# 03_BOOT.net
KiCad netlist of a schematic drawn in Altium Designer
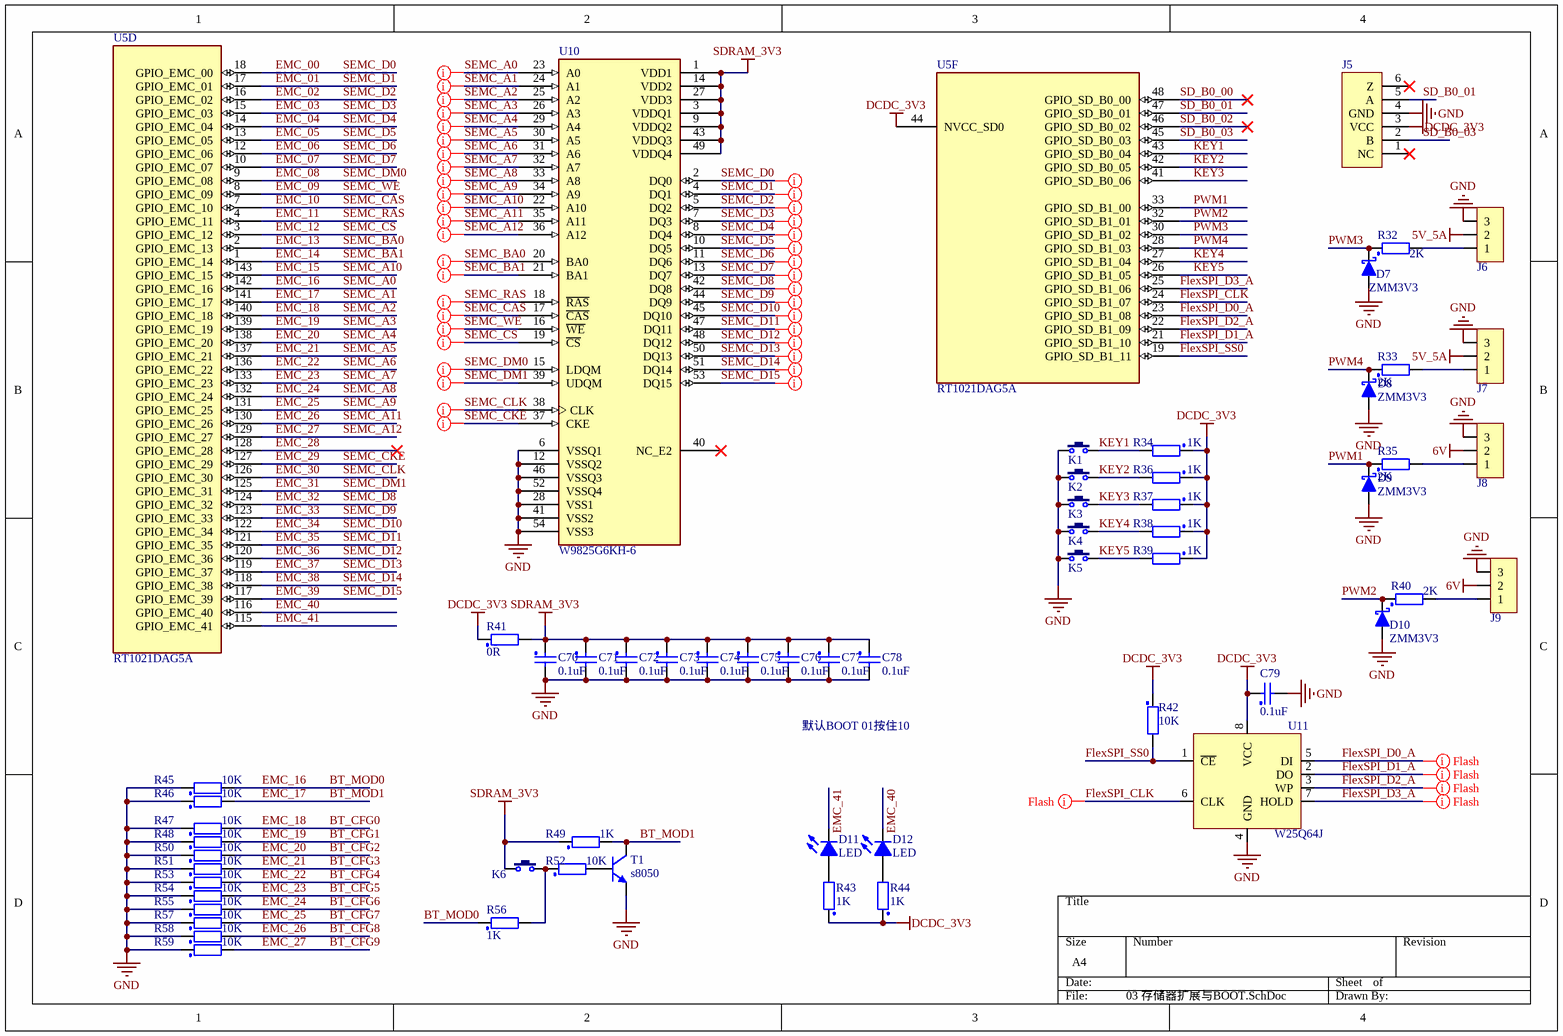
[diagram p0: 03 存储器扩展与BOOT.SchDoc]

(export (version "E")
  (design (tool "Eeschema 10.0.6"))
  (components
    (comp (ref "C70")
      (value "0.1uF")
      (footprint "cap0603")
      (description "贴片电容")
      (fields (field (name "PUBLISHER") "Altium Limited"))
      (libsource (lib "元件库") (part "Cap"))
    )
    (comp (ref "C71")
      (value "0.1uF")
      (footprint "cap0603")
      (description "贴片电容")
      (fields (field (name "PUBLISHER") "Altium Limited"))
      (libsource (lib "元件库") (part "Cap"))
    )
    (comp (ref "C72")
      (value "0.1uF")
      (footprint "cap0603")
      (description "贴片电容")
      (fields (field (name "PUBLISHER") "Altium Limited"))
      (libsource (lib "元件库") (part "Cap"))
    )
    (comp (ref "C73")
      (value "0.1uF")
      (footprint "cap0603")
      (description "贴片电容")
      (fields (field (name "PUBLISHER") "Altium Limited"))
      (libsource (lib "元件库") (part "Cap"))
    )
    (comp (ref "C74")
      (value "0.1uF")
      (footprint "cap0603")
      (description "贴片电容")
      (fields (field (name "PUBLISHER") "Altium Limited"))
      (libsource (lib "元件库") (part "Cap"))
    )
    (comp (ref "C75")
      (value "0.1uF")
      (footprint "cap0603")
      (description "贴片电容")
      (fields (field (name "PUBLISHER") "Altium Limited"))
      (libsource (lib "元件库") (part "Cap"))
    )
    (comp (ref "C76")
      (value "0.1uF")
      (footprint "cap0603")
      (description "贴片电容")
      (fields (field (name "PUBLISHER") "Altium Limited"))
      (libsource (lib "元件库") (part "Cap"))
    )
    (comp (ref "C77")
      (value "0.1uF")
      (footprint "cap0603")
      (description "贴片电容")
      (fields (field (name "PUBLISHER") "Altium Limited"))
      (libsource (lib "元件库") (part "Cap"))
    )
    (comp (ref "C78")
      (value "0.1uF")
      (footprint "cap0603")
      (description "贴片电容")
      (fields (field (name "PUBLISHER") "Altium Limited"))
      (libsource (lib "元件库") (part "Cap"))
    )
    (comp (ref "C79")
      (value "0.1uF")
      (footprint "cap0603")
      (description "贴片电容")
      (fields (field (name "PUBLISHER") "Altium Limited"))
      (libsource (lib "元件库") (part "Cap"))
    )
    (comp (ref "D7")
      (value "ZMM3V3")
      (footprint "LL34")
      (description "稳压二极管")
      (fields (field (name "PUBLISHER") "Altium Limited"))
      (libsource (lib "元件库") (part "D Schottky"))
    )
    (comp (ref "D8")
      (value "ZMM3V3")
      (footprint "LL34")
      (description "稳压二极管")
      (fields (field (name "PUBLISHER") "Altium Limited"))
      (libsource (lib "元件库") (part "D Schottky"))
    )
    (comp (ref "D9")
      (value "ZMM3V3")
      (footprint "LL34")
      (description "稳压二极管")
      (fields (field (name "PUBLISHER") "Altium Limited"))
      (libsource (lib "元件库") (part "D Schottky"))
    )
    (comp (ref "D10")
      (value "ZMM3V3")
      (footprint "LL34")
      (description "稳压二极管")
      (fields (field (name "PUBLISHER") "Altium Limited"))
      (libsource (lib "元件库") (part "D Schottky"))
    )
    (comp (ref "D11")
      (value "LED")
      (footprint "LED")
      (description "贴片LED")
      (fields (field (name "PUBLISHER") "Altium Limited"))
      (libsource (lib "元件库") (part "LED"))
    )
    (comp (ref "D12")
      (value "LED")
      (footprint "LED")
      (description "贴片LED")
      (fields (field (name "PUBLISHER") "Altium Limited"))
      (libsource (lib "元件库") (part "LED"))
    )
    (comp (ref "J5")
      (value "2x6")
      (footprint "LQ256Encoder")
      (description "2.54mm公排针")
      (libsource (lib "元件库") (part "LQ_AB256"))
    )
    (comp (ref "J6")
      (value "1X3")
      (footprint "HDR-1X3")
      (description "2.54mm公排针")
      (fields (field (name "版权归属") "源创客"))
      (libsource (lib "元件库") (part "Header 3"))
    )
    (comp (ref "J7")
      (value "1X3")
      (footprint "HDR-1X3")
      (description "2.54mm公排针")
      (fields (field (name "版权归属") "源创客"))
      (libsource (lib "元件库") (part "Header 3"))
    )
    (comp (ref "J8")
      (value "1X3")
      (footprint "HDR-1X3")
      (description "2.54mm公排针")
      (fields (field (name "版权归属") "源创客"))
      (libsource (lib "元件库") (part "Header 3"))
    )
    (comp (ref "J9")
      (value "1X3")
      (footprint "HDR-1X3")
      (description "2.54mm公排针")
      (fields (field (name "版权归属") "源创客"))
      (libsource (lib "元件库") (part "Header 3"))
    )
    (comp (ref "K1")
      (value "KEY")
      (footprint "key")
      (description "按键")
      (fields (field (name "版权归属") "源创客"))
      (libsource (lib "元件库") (part "KEY"))
    )
    (comp (ref "K2")
      (value "KEY")
      (footprint "key")
      (description "按键")
      (fields (field (name "版权归属") "源创客"))
      (libsource (lib "元件库") (part "KEY"))
    )
    (comp (ref "K3")
      (value "KEY")
      (footprint "key")
      (description "按键")
      (fields (field (name "版权归属") "源创客"))
      (libsource (lib "元件库") (part "KEY"))
    )
    (comp (ref "K4")
      (value "KEY")
      (footprint "key")
      (description "按键")
      (fields (field (name "版权归属") "源创客"))
      (libsource (lib "元件库") (part "KEY"))
    )
    (comp (ref "K5")
      (value "KEY")
      (footprint "key")
      (description "按键")
      (fields (field (name "版权归属") "源创客"))
      (libsource (lib "元件库") (part "KEY"))
    )
    (comp (ref "K6")
      (value "KEY")
      (footprint "key")
      (description "按键")
      (fields (field (name "版权归属") "源创客"))
      (libsource (lib "元件库") (part "KEY"))
    )
    (comp (ref "R32")
      (value "2K")
      (footprint "res0603")
      (description "贴片电阻")
      (fields (field (name "PUBLISHER") "Altium Limited"))
      (libsource (lib "") (part "Res_1"))
    )
    (comp (ref "R33")
      (value "2K")
      (footprint "res0603")
      (description "贴片电阻")
      (fields (field (name "PUBLISHER") "Altium Limited"))
      (libsource (lib "") (part "Res_1"))
    )
    (comp (ref "R34")
      (value "1K")
      (footprint "res0603")
      (description "贴片电阻")
      (fields (field (name "PUBLISHER") "Altium Limited"))
      (libsource (lib "") (part "Res_2"))
    )
    (comp (ref "R35")
      (value "2K")
      (footprint "res0603")
      (description "贴片电阻")
      (fields (field (name "PUBLISHER") "Altium Limited"))
      (libsource (lib "") (part "Res_1"))
    )
    (comp (ref "R36")
      (value "1K")
      (footprint "res0603")
      (description "贴片电阻")
      (fields (field (name "PUBLISHER") "Altium Limited"))
      (libsource (lib "") (part "Res_2"))
    )
    (comp (ref "R37")
      (value "1K")
      (footprint "res0603")
      (description "贴片电阻")
      (fields (field (name "PUBLISHER") "Altium Limited"))
      (libsource (lib "") (part "Res_2"))
    )
    (comp (ref "R38")
      (value "1K")
      (footprint "res0603")
      (description "贴片电阻")
      (fields (field (name "PUBLISHER") "Altium Limited"))
      (libsource (lib "") (part "Res_2"))
    )
    (comp (ref "R39")
      (value "1K")
      (footprint "res0603")
      (description "贴片电阻")
      (fields (field (name "PUBLISHER") "Altium Limited"))
      (libsource (lib "") (part "Res_2"))
    )
    (comp (ref "R40")
      (value "2K")
      (footprint "res0603")
      (description "贴片电阻")
      (fields (field (name "PUBLISHER") "Altium Limited"))
      (libsource (lib "") (part "Res_1"))
    )
    (comp (ref "R41")
      (value "0R")
      (footprint "res0603")
      (description "贴片电阻")
      (fields (field (name "PUBLISHER") "Altium Limited"))
      (libsource (lib "") (part "Res_1"))
    )
    (comp (ref "R42")
      (value "10K")
      (footprint "res0603")
      (description "贴片电阻")
      (fields (field (name "PUBLISHER") "Altium Limited"))
      (libsource (lib "元件库") (part "Res"))
    )
    (comp (ref "R43")
      (value "1K")
      (footprint "res0603")
      (description "贴片电阻")
      (fields (field (name "PUBLISHER") "Altium Limited"))
      (libsource (lib "") (part "Res_3"))
    )
    (comp (ref "R44")
      (value "1K")
      (footprint "res0603")
      (description "贴片电阻")
      (fields (field (name "PUBLISHER") "Altium Limited"))
      (libsource (lib "") (part "Res_3"))
    )
    (comp (ref "R45")
      (value "10K")
      (footprint "res0603")
      (description "贴片电阻")
      (fields (field (name "PUBLISHER") "Altium Limited"))
      (libsource (lib "") (part "Res_1"))
    )
    (comp (ref "R46")
      (value "10K")
      (footprint "res0603")
      (description "贴片电阻")
      (fields (field (name "PUBLISHER") "Altium Limited"))
      (libsource (lib "") (part "Res_1"))
    )
    (comp (ref "R47")
      (value "10K")
      (footprint "res0603")
      (description "贴片电阻")
      (fields (field (name "PUBLISHER") "Altium Limited"))
      (libsource (lib "") (part "Res_1"))
    )
    (comp (ref "R48")
      (value "10K")
      (footprint "res0603")
      (description "贴片电阻")
      (fields (field (name "PUBLISHER") "Altium Limited"))
      (libsource (lib "") (part "Res_1"))
    )
    (comp (ref "R49")
      (value "1K")
      (footprint "res0603")
      (description "贴片电阻")
      (fields (field (name "PUBLISHER") "Altium Limited"))
      (libsource (lib "") (part "Res_1"))
    )
    (comp (ref "R50")
      (value "10K")
      (footprint "res0603")
      (description "贴片电阻")
      (fields (field (name "PUBLISHER") "Altium Limited"))
      (libsource (lib "") (part "Res_1"))
    )
    (comp (ref "R51")
      (value "10K")
      (footprint "res0603")
      (description "贴片电阻")
      (fields (field (name "PUBLISHER") "Altium Limited"))
      (libsource (lib "") (part "Res_1"))
    )
    (comp (ref "R52")
      (value "10K")
      (footprint "res0603")
      (description "贴片电阻")
      (fields (field (name "PUBLISHER") "Altium Limited"))
      (libsource (lib "") (part "Res_1"))
    )
    (comp (ref "R53")
      (value "10K")
      (footprint "res0603")
      (description "贴片电阻")
      (fields (field (name "PUBLISHER") "Altium Limited"))
      (libsource (lib "") (part "Res_1"))
    )
    (comp (ref "R54")
      (value "10K")
      (footprint "res0603")
      (description "贴片电阻")
      (fields (field (name "PUBLISHER") "Altium Limited"))
      (libsource (lib "") (part "Res_1"))
    )
    (comp (ref "R55")
      (value "10K")
      (footprint "res0603")
      (description "贴片电阻")
      (fields (field (name "PUBLISHER") "Altium Limited"))
      (libsource (lib "") (part "Res_1"))
    )
    (comp (ref "R56")
      (value "1K")
      (footprint "res0603")
      (description "贴片电阻")
      (fields (field (name "PUBLISHER") "Altium Limited"))
      (libsource (lib "") (part "Res_1"))
    )
    (comp (ref "R57")
      (value "10K")
      (footprint "res0603")
      (description "贴片电阻")
      (fields (field (name "PUBLISHER") "Altium Limited"))
      (libsource (lib "") (part "Res_1"))
    )
    (comp (ref "R58")
      (value "10K")
      (footprint "res0603")
      (description "贴片电阻")
      (fields (field (name "PUBLISHER") "Altium Limited"))
      (libsource (lib "") (part "Res_1"))
    )
    (comp (ref "R59")
      (value "10K")
      (footprint "res0603")
      (description "贴片电阻")
      (fields (field (name "PUBLISHER") "Altium Limited"))
      (libsource (lib "") (part "Res_1"))
    )
    (comp (ref "T1")
      (value "s8050")
      (footprint "SOT-23-3")
      (description "贴片三极管 NPN管")
      (libsource (lib "元件库") (part "s8050"))
    )
    (comp (ref "U5")
      (value "RT1021DAG5A")
      (footprint "LQFP144")
      (description "Cortex-M7 500MHZ 1.3V")
      (libsource (lib "元件库") (part "RT1021DAG5A"))
    )
    (comp (ref "U10")
      (value "W9825G6KH-6")
      (footprint "TSOP(II)-54")
      (description "SDRAM 16MX16 6NS 3.3V TSOP(II)-54")
      (libsource (lib "元件库") (part "W9825G6KH-6"))
    )
    (comp (ref "U11")
      (value "W25Q64J")
      (footprint "SOIC8-208mil")
      (description "flash")
      (libsource (lib "元件库") (part "W25Q"))
    )
  )
  (nets
    (net (code "1") (name "/BT_CFG0") (class "Default")
      (node (ref "R47") (pin "2") (pinfunction "2_2") (pintype "passive"))
      (node (ref "U10") (pin "25") (pinfunction "A2_25") (pintype "input"))
      (node (ref "U5") (pin "140") (pinfunction "GPIO_EMC_18_140") (pintype "bidirectional"))
    )
    (net (code "2") (name "/BT_CFG1") (class "Default")
      (node (ref "R48") (pin "2") (pinfunction "2_2") (pintype "passive"))
      (node (ref "U10") (pin "26") (pinfunction "A3_26") (pintype "input"))
      (node (ref "U5") (pin "139") (pinfunction "GPIO_EMC_19_139") (pintype "bidirectional"))
    )
    (net (code "3") (name "/BT_CFG2") (class "Default")
      (node (ref "R50") (pin "2") (pinfunction "2_2") (pintype "passive"))
      (node (ref "U10") (pin "29") (pinfunction "A4_29") (pintype "input"))
      (node (ref "U5") (pin "138") (pinfunction "GPIO_EMC_20_138") (pintype "bidirectional"))
    )
    (net (code "4") (name "/BT_CFG3") (class "Default")
      (node (ref "R51") (pin "2") (pinfunction "2_2") (pintype "passive"))
      (node (ref "U10") (pin "30") (pinfunction "A5_30") (pintype "input"))
      (node (ref "U5") (pin "137") (pinfunction "GPIO_EMC_21_137") (pintype "bidirectional"))
    )
    (net (code "5") (name "/BT_CFG4") (class "Default")
      (node (ref "R53") (pin "2") (pinfunction "2_2") (pintype "passive"))
      (node (ref "U10") (pin "31") (pinfunction "A6_31") (pintype "input"))
      (node (ref "U5") (pin "136") (pinfunction "GPIO_EMC_22_136") (pintype "bidirectional"))
    )
    (net (code "6") (name "/BT_CFG5") (class "Default")
      (node (ref "R54") (pin "2") (pinfunction "2_2") (pintype "passive"))
      (node (ref "U10") (pin "32") (pinfunction "A7_32") (pintype "input"))
      (node (ref "U5") (pin "133") (pinfunction "GPIO_EMC_23_133") (pintype "bidirectional"))
    )
    (net (code "7") (name "/BT_CFG6") (class "Default")
      (node (ref "R55") (pin "2") (pinfunction "2_2") (pintype "passive"))
      (node (ref "U10") (pin "33") (pinfunction "A8_33") (pintype "input"))
      (node (ref "U5") (pin "132") (pinfunction "GPIO_EMC_24_132") (pintype "bidirectional"))
    )
    (net (code "8") (name "/BT_CFG7") (class "Default")
      (node (ref "R57") (pin "2") (pinfunction "2_2") (pintype "passive"))
      (node (ref "U10") (pin "34") (pinfunction "A9_34") (pintype "input"))
      (node (ref "U5") (pin "131") (pinfunction "GPIO_EMC_25_131") (pintype "bidirectional"))
    )
    (net (code "9") (name "/BT_CFG8") (class "Default")
      (node (ref "R58") (pin "2") (pinfunction "2_2") (pintype "passive"))
      (node (ref "U10") (pin "35") (pinfunction "A11_35") (pintype "input"))
      (node (ref "U5") (pin "130") (pinfunction "GPIO_EMC_26_130") (pintype "bidirectional"))
    )
    (net (code "10") (name "/BT_CFG9") (class "Default")
      (node (ref "R59") (pin "2") (pinfunction "2_2") (pintype "passive"))
      (node (ref "U10") (pin "36") (pinfunction "A12_36") (pintype "input"))
      (node (ref "U5") (pin "129") (pinfunction "GPIO_EMC_27_129") (pintype "bidirectional"))
    )
    (net (code "11") (name "/BT_MOD0") (class "Default")
      (node (ref "R45") (pin "2") (pinfunction "2_2") (pintype "passive"))
      (node (ref "R56") (pin "1") (pinfunction "1_1") (pintype "passive"))
      (node (ref "U10") (pin "23") (pinfunction "A0_23") (pintype "input"))
      (node (ref "U5") (pin "142") (pinfunction "GPIO_EMC_16_142") (pintype "bidirectional"))
    )
    (net (code "12") (name "/BT_MOD1") (class "Default")
      (node (ref "R46") (pin "2") (pinfunction "2_2") (pintype "passive"))
      (node (ref "R49") (pin "2") (pinfunction "2_2") (pintype "passive"))
      (node (ref "T1") (pin "3") (pinfunction "C_3") (pintype "passive"))
      (node (ref "U10") (pin "24") (pinfunction "A1_24") (pintype "input"))
      (node (ref "U5") (pin "141") (pinfunction "GPIO_EMC_17_141") (pintype "bidirectional"))
    )
    (net (code "13") (name "/EMC_00") (class "Default")
      (node (ref "U10") (pin "2") (pinfunction "DQ0_2") (pintype "bidirectional"))
      (node (ref "U5") (pin "18") (pinfunction "GPIO_EMC_00_18") (pintype "bidirectional"))
    )
    (net (code "14") (name "/EMC_01") (class "Default")
      (node (ref "U10") (pin "4") (pinfunction "DQ1_4") (pintype "bidirectional"))
      (node (ref "U5") (pin "17") (pinfunction "GPIO_EMC_01_17") (pintype "bidirectional"))
    )
    (net (code "15") (name "/EMC_02") (class "Default")
      (node (ref "U10") (pin "5") (pinfunction "DQ2_5") (pintype "bidirectional"))
      (node (ref "U5") (pin "16") (pinfunction "GPIO_EMC_02_16") (pintype "bidirectional"))
    )
    (net (code "16") (name "/EMC_03") (class "Default")
      (node (ref "U10") (pin "7") (pinfunction "DQ3_7") (pintype "bidirectional"))
      (node (ref "U5") (pin "15") (pinfunction "GPIO_EMC_03_15") (pintype "bidirectional"))
    )
    (net (code "17") (name "/EMC_04") (class "Default")
      (node (ref "U10") (pin "8") (pinfunction "DQ4_8") (pintype "bidirectional"))
      (node (ref "U5") (pin "14") (pinfunction "GPIO_EMC_04_14") (pintype "bidirectional"))
    )
    (net (code "18") (name "/EMC_05") (class "Default")
      (node (ref "U10") (pin "10") (pinfunction "DQ5_10") (pintype "bidirectional"))
      (node (ref "U5") (pin "13") (pinfunction "GPIO_EMC_05_13") (pintype "bidirectional"))
    )
    (net (code "19") (name "/EMC_06") (class "Default")
      (node (ref "U10") (pin "11") (pinfunction "DQ6_11") (pintype "bidirectional"))
      (node (ref "U5") (pin "12") (pinfunction "GPIO_EMC_06_12") (pintype "bidirectional"))
    )
    (net (code "20") (name "/EMC_07") (class "Default")
      (node (ref "U10") (pin "13") (pinfunction "DQ7_13") (pintype "bidirectional"))
      (node (ref "U5") (pin "10") (pinfunction "GPIO_EMC_07_10") (pintype "bidirectional"))
    )
    (net (code "21") (name "/EMC_08") (class "Default")
      (node (ref "U10") (pin "15") (pinfunction "LDQM_15") (pintype "input"))
      (node (ref "U5") (pin "9") (pinfunction "GPIO_EMC_08_9") (pintype "bidirectional"))
    )
    (net (code "22") (name "/EMC_09") (class "Default")
      (node (ref "U10") (pin "16") (pinfunction "~{WE}_16") (pintype "input"))
      (node (ref "U5") (pin "8") (pinfunction "GPIO_EMC_09_8") (pintype "bidirectional"))
    )
    (net (code "23") (name "/EMC_10") (class "Default")
      (node (ref "U10") (pin "17") (pinfunction "~{CAS}_17") (pintype "input"))
      (node (ref "U5") (pin "7") (pinfunction "GPIO_EMC_10_7") (pintype "bidirectional"))
    )
    (net (code "24") (name "/EMC_11") (class "Default")
      (node (ref "U10") (pin "18") (pinfunction "~{RAS}_18") (pintype "input"))
      (node (ref "U5") (pin "4") (pinfunction "GPIO_EMC_11_4") (pintype "bidirectional"))
    )
    (net (code "25") (name "/EMC_12") (class "Default")
      (node (ref "U10") (pin "19") (pinfunction "~{CS}_19") (pintype "input"))
      (node (ref "U5") (pin "3") (pinfunction "GPIO_EMC_12_3") (pintype "bidirectional"))
    )
    (net (code "26") (name "/EMC_13") (class "Default")
      (node (ref "U10") (pin "20") (pinfunction "BA0_20") (pintype "input"))
      (node (ref "U5") (pin "2") (pinfunction "GPIO_EMC_13_2") (pintype "bidirectional"))
    )
    (net (code "27") (name "/EMC_14") (class "Default")
      (node (ref "U10") (pin "21") (pinfunction "BA1_21") (pintype "input"))
      (node (ref "U5") (pin "1") (pinfunction "GPIO_EMC_14_1") (pintype "bidirectional"))
    )
    (net (code "28") (name "/EMC_15") (class "Default")
      (node (ref "U10") (pin "22") (pinfunction "A10_22") (pintype "input"))
      (node (ref "U5") (pin "143") (pinfunction "GPIO_EMC_15_143") (pintype "bidirectional"))
    )
    (net (code "29") (name "/EMC_28") (class "Default")
      (node (ref "U5") (pin "128") (pinfunction "GPIO_EMC_28_128") (pintype "bidirectional+no_connect"))
    )
    (net (code "30") (name "/EMC_29") (class "Default")
      (node (ref "U10") (pin "37") (pinfunction "CKE_37") (pintype "input"))
      (node (ref "U5") (pin "127") (pinfunction "GPIO_EMC_29_127") (pintype "bidirectional"))
    )
    (net (code "31") (name "/EMC_30") (class "Default")
      (node (ref "U10") (pin "38") (pinfunction "CLK_38") (pintype "input"))
      (node (ref "U5") (pin "126") (pinfunction "GPIO_EMC_30_126") (pintype "bidirectional"))
    )
    (net (code "32") (name "/EMC_31") (class "Default")
      (node (ref "U10") (pin "39") (pinfunction "UDQM_39") (pintype "input"))
      (node (ref "U5") (pin "125") (pinfunction "GPIO_EMC_31_125") (pintype "bidirectional"))
    )
    (net (code "33") (name "/EMC_32") (class "Default")
      (node (ref "U10") (pin "42") (pinfunction "DQ8_42") (pintype "bidirectional"))
      (node (ref "U5") (pin "124") (pinfunction "GPIO_EMC_32_124") (pintype "bidirectional"))
    )
    (net (code "34") (name "/EMC_33") (class "Default")
      (node (ref "U10") (pin "44") (pinfunction "DQ9_44") (pintype "bidirectional"))
      (node (ref "U5") (pin "123") (pinfunction "GPIO_EMC_33_123") (pintype "bidirectional"))
    )
    (net (code "35") (name "/EMC_34") (class "Default")
      (node (ref "U10") (pin "45") (pinfunction "DQ10_45") (pintype "bidirectional"))
      (node (ref "U5") (pin "122") (pinfunction "GPIO_EMC_34_122") (pintype "bidirectional"))
    )
    (net (code "36") (name "/EMC_35") (class "Default")
      (node (ref "U10") (pin "47") (pinfunction "DQ11_47") (pintype "bidirectional"))
      (node (ref "U5") (pin "121") (pinfunction "GPIO_EMC_35_121") (pintype "bidirectional"))
    )
    (net (code "37") (name "/EMC_36") (class "Default")
      (node (ref "U10") (pin "48") (pinfunction "DQ12_48") (pintype "bidirectional"))
      (node (ref "U5") (pin "120") (pinfunction "GPIO_EMC_36_120") (pintype "bidirectional"))
    )
    (net (code "38") (name "/EMC_37") (class "Default")
      (node (ref "U10") (pin "50") (pinfunction "DQ13_50") (pintype "bidirectional"))
      (node (ref "U5") (pin "119") (pinfunction "GPIO_EMC_37_119") (pintype "bidirectional"))
    )
    (net (code "39") (name "/EMC_38") (class "Default")
      (node (ref "U10") (pin "51") (pinfunction "DQ14_51") (pintype "bidirectional"))
      (node (ref "U5") (pin "118") (pinfunction "GPIO_EMC_38_118") (pintype "bidirectional"))
    )
    (net (code "40") (name "/EMC_39") (class "Default")
      (node (ref "U10") (pin "53") (pinfunction "DQ15_53") (pintype "bidirectional"))
      (node (ref "U5") (pin "117") (pinfunction "GPIO_EMC_39_117") (pintype "bidirectional"))
    )
    (net (code "41") (name "/EMC_40") (class "Default")
      (node (ref "D12") (pin "2") (pinfunction "K_2") (pintype "passive"))
      (node (ref "U5") (pin "116") (pinfunction "GPIO_EMC_40_116") (pintype "bidirectional"))
    )
    (net (code "42") (name "/EMC_41") (class "Default")
      (node (ref "D11") (pin "2") (pinfunction "K_2") (pintype "passive"))
      (node (ref "U5") (pin "115") (pinfunction "GPIO_EMC_41_115") (pintype "bidirectional"))
    )
    (net (code "43") (name "/FlexSPI_CLK") (class "Default")
      (node (ref "U11") (pin "6") (pinfunction "CLK_6") (pintype "passive"))
      (node (ref "U5") (pin "24") (pinfunction "GPIO_SD_B1_07_24") (pintype "bidirectional"))
    )
    (net (code "44") (name "/FlexSPI_D0_A") (class "Default")
      (node (ref "U11") (pin "5") (pinfunction "DI_5") (pintype "passive"))
      (node (ref "U5") (pin "23") (pinfunction "GPIO_SD_B1_08_23") (pintype "bidirectional"))
    )
    (net (code "45") (name "/FlexSPI_D1_A") (class "Default")
      (node (ref "U11") (pin "2") (pinfunction "DO_2") (pintype "passive"))
      (node (ref "U5") (pin "21") (pinfunction "GPIO_SD_B1_10_21") (pintype "bidirectional"))
    )
    (net (code "46") (name "/FlexSPI_D2_A") (class "Default")
      (node (ref "U11") (pin "3") (pinfunction "WP_3") (pintype "passive"))
      (node (ref "U5") (pin "22") (pinfunction "GPIO_SD_B1_09_22") (pintype "bidirectional"))
    )
    (net (code "47") (name "/FlexSPI_D3_A") (class "Default")
      (node (ref "U11") (pin "7") (pinfunction "HOLD_7") (pintype "passive"))
      (node (ref "U5") (pin "25") (pinfunction "GPIO_SD_B1_06_25") (pintype "bidirectional"))
    )
    (net (code "48") (name "/FlexSPI_SS0") (class "Default")
      (node (ref "R42") (pin "2") (pinfunction "2_2") (pintype "passive"))
      (node (ref "U11") (pin "1") (pinfunction "~{CE}_1") (pintype "passive"))
      (node (ref "U5") (pin "19") (pinfunction "GPIO_SD_B1_11_19") (pintype "bidirectional"))
    )
    (net (code "49") (name "/KEY1") (class "Default")
      (node (ref "K1") (pin "2") (pinfunction "2_2") (pintype "passive"))
      (node (ref "R34") (pin "2") (pinfunction "2_2") (pintype "passive"))
      (node (ref "U5") (pin "43") (pinfunction "GPIO_SD_B0_04_43") (pintype "bidirectional"))
    )
    (net (code "50") (name "/KEY2") (class "Default")
      (node (ref "K2") (pin "2") (pinfunction "2_2") (pintype "passive"))
      (node (ref "R36") (pin "2") (pinfunction "2_2") (pintype "passive"))
      (node (ref "U5") (pin "42") (pinfunction "GPIO_SD_B0_05_42") (pintype "bidirectional"))
    )
    (net (code "51") (name "/KEY3") (class "Default")
      (node (ref "K3") (pin "2") (pinfunction "2_2") (pintype "passive"))
      (node (ref "R37") (pin "2") (pinfunction "2_2") (pintype "passive"))
      (node (ref "U5") (pin "41") (pinfunction "GPIO_SD_B0_06_41") (pintype "bidirectional"))
    )
    (net (code "52") (name "/KEY4") (class "Default")
      (node (ref "K4") (pin "2") (pinfunction "2_2") (pintype "passive"))
      (node (ref "R38") (pin "2") (pinfunction "2_2") (pintype "passive"))
      (node (ref "U5") (pin "27") (pinfunction "GPIO_SD_B1_04_27") (pintype "bidirectional"))
    )
    (net (code "53") (name "/KEY5") (class "Default")
      (node (ref "K5") (pin "2") (pinfunction "2_2") (pintype "passive"))
      (node (ref "R39") (pin "2") (pinfunction "2_2") (pintype "passive"))
      (node (ref "U5") (pin "26") (pinfunction "GPIO_SD_B1_05_26") (pintype "bidirectional"))
    )
    (net (code "54") (name "/PWM1") (class "Default")
      (node (ref "D9") (pin "2") (pinfunction "K_2") (pintype "passive"))
      (node (ref "R35") (pin "1") (pinfunction "1_1") (pintype "passive"))
      (node (ref "U5") (pin "33") (pinfunction "GPIO_SD_B1_00_33") (pintype "bidirectional"))
    )
    (net (code "55") (name "/PWM2") (class "Default")
      (node (ref "D10") (pin "2") (pinfunction "K_2") (pintype "passive"))
      (node (ref "R40") (pin "1") (pinfunction "1_1") (pintype "passive"))
      (node (ref "U5") (pin "32") (pinfunction "GPIO_SD_B1_01_32") (pintype "bidirectional"))
    )
    (net (code "56") (name "/PWM3") (class "Default")
      (node (ref "D7") (pin "2") (pinfunction "K_2") (pintype "passive"))
      (node (ref "R32") (pin "1") (pinfunction "1_1") (pintype "passive"))
      (node (ref "U5") (pin "30") (pinfunction "GPIO_SD_B1_02_30") (pintype "bidirectional"))
    )
    (net (code "57") (name "/PWM4") (class "Default")
      (node (ref "D8") (pin "2") (pinfunction "K_2") (pintype "passive"))
      (node (ref "R33") (pin "1") (pinfunction "1_1") (pintype "passive"))
      (node (ref "U5") (pin "28") (pinfunction "GPIO_SD_B1_03_28") (pintype "bidirectional"))
    )
    (net (code "58") (name "/SD_B0_00") (class "Default")
      (node (ref "U5") (pin "48") (pinfunction "GPIO_SD_B0_00_48") (pintype "bidirectional+no_connect"))
    )
    (net (code "59") (name "/SD_B0_01") (class "Default")
      (node (ref "J5") (pin "5") (pinfunction "A_5") (pintype "passive"))
      (node (ref "U5") (pin "47") (pinfunction "GPIO_SD_B0_01_47") (pintype "bidirectional"))
    )
    (net (code "60") (name "/SD_B0_02") (class "Default")
      (node (ref "U5") (pin "46") (pinfunction "GPIO_SD_B0_02_46") (pintype "bidirectional+no_connect"))
    )
    (net (code "61") (name "/SD_B0_03") (class "Default")
      (node (ref "J5") (pin "2") (pinfunction "B_2") (pintype "passive"))
      (node (ref "U5") (pin "45") (pinfunction "GPIO_SD_B0_03_45") (pintype "bidirectional"))
    )
    (net (code "62") (name "5V_5A") (class "Default")
      (node (ref "J6") (pin "2") (pinfunction "2_2") (pintype "passive"))
      (node (ref "J7") (pin "2") (pinfunction "2_2") (pintype "passive"))
    )
    (net (code "63") (name "6V") (class "Default")
      (node (ref "J8") (pin "2") (pinfunction "2_2") (pintype "passive"))
      (node (ref "J9") (pin "2") (pinfunction "2_2") (pintype "passive"))
    )
    (net (code "64") (name "DCDC_3V3") (class "Default")
      (node (ref "C79") (pin "1") (pinfunction "1_1") (pintype "passive"))
      (node (ref "J5") (pin "3") (pinfunction "VCC_3") (pintype "passive"))
      (node (ref "R34") (pin "1") (pinfunction "1_1") (pintype "passive"))
      (node (ref "R36") (pin "1") (pinfunction "1_1") (pintype "passive"))
      (node (ref "R37") (pin "1") (pinfunction "1_1") (pintype "passive"))
      (node (ref "R38") (pin "1") (pinfunction "1_1") (pintype "passive"))
      (node (ref "R39") (pin "1") (pinfunction "1_1") (pintype "passive"))
      (node (ref "R41") (pin "1") (pinfunction "1_1") (pintype "passive"))
      (node (ref "R42") (pin "1") (pinfunction "1_1") (pintype "passive"))
      (node (ref "R43") (pin "1") (pinfunction "1_1") (pintype "passive"))
      (node (ref "R44") (pin "1") (pinfunction "1_1") (pintype "passive"))
      (node (ref "U11") (pin "8") (pinfunction "VCC_8") (pintype "passive"))
      (node (ref "U5") (pin "44") (pinfunction "NVCC_SD0_44") (pintype "power_in"))
    )
    (net (code "65") (name "GND") (class "Default")
      (node (ref "C70") (pin "2") (pinfunction "2_2") (pintype "passive"))
      (node (ref "C71") (pin "2") (pinfunction "2_2") (pintype "passive"))
      (node (ref "C72") (pin "2") (pinfunction "2_2") (pintype "passive"))
      (node (ref "C73") (pin "2") (pinfunction "2_2") (pintype "passive"))
      (node (ref "C74") (pin "2") (pinfunction "2_2") (pintype "passive"))
      (node (ref "C75") (pin "2") (pinfunction "2_2") (pintype "passive"))
      (node (ref "C76") (pin "2") (pinfunction "2_2") (pintype "passive"))
      (node (ref "C77") (pin "2") (pinfunction "2_2") (pintype "passive"))
      (node (ref "C78") (pin "2") (pinfunction "2_2") (pintype "passive"))
      (node (ref "C79") (pin "2") (pinfunction "2_2") (pintype "passive"))
      (node (ref "D10") (pin "1") (pinfunction "A_1") (pintype "passive"))
      (node (ref "D7") (pin "1") (pinfunction "A_1") (pintype "passive"))
      (node (ref "D8") (pin "1") (pinfunction "A_1") (pintype "passive"))
      (node (ref "D9") (pin "1") (pinfunction "A_1") (pintype "passive"))
      (node (ref "J5") (pin "4") (pinfunction "GND_4") (pintype "passive"))
      (node (ref "J6") (pin "3") (pinfunction "3_3") (pintype "passive"))
      (node (ref "J7") (pin "3") (pinfunction "3_3") (pintype "passive"))
      (node (ref "J8") (pin "3") (pinfunction "3_3") (pintype "passive"))
      (node (ref "J9") (pin "3") (pinfunction "3_3") (pintype "passive"))
      (node (ref "K1") (pin "1") (pinfunction "1_1") (pintype "passive"))
      (node (ref "K2") (pin "1") (pinfunction "1_1") (pintype "passive"))
      (node (ref "K3") (pin "1") (pinfunction "1_1") (pintype "passive"))
      (node (ref "K4") (pin "1") (pinfunction "1_1") (pintype "passive"))
      (node (ref "K5") (pin "1") (pinfunction "1_1") (pintype "passive"))
      (node (ref "R45") (pin "1") (pinfunction "1_1") (pintype "passive"))
      (node (ref "R46") (pin "1") (pinfunction "1_1") (pintype "passive"))
      (node (ref "R47") (pin "1") (pinfunction "1_1") (pintype "passive"))
      (node (ref "R48") (pin "1") (pinfunction "1_1") (pintype "passive"))
      (node (ref "R50") (pin "1") (pinfunction "1_1") (pintype "passive"))
      (node (ref "R51") (pin "1") (pinfunction "1_1") (pintype "passive"))
      (node (ref "R53") (pin "1") (pinfunction "1_1") (pintype "passive"))
      (node (ref "R54") (pin "1") (pinfunction "1_1") (pintype "passive"))
      (node (ref "R55") (pin "1") (pinfunction "1_1") (pintype "passive"))
      (node (ref "R57") (pin "1") (pinfunction "1_1") (pintype "passive"))
      (node (ref "R58") (pin "1") (pinfunction "1_1") (pintype "passive"))
      (node (ref "R59") (pin "1") (pinfunction "1_1") (pintype "passive"))
      (node (ref "T1") (pin "2") (pinfunction "E_2") (pintype "passive"))
      (node (ref "U10") (pin "12") (pinfunction "VSSQ2_12") (pintype "power_in"))
      (node (ref "U10") (pin "28") (pinfunction "VSS1_28") (pintype "power_in"))
      (node (ref "U10") (pin "41") (pinfunction "VSS2_41") (pintype "power_in"))
      (node (ref "U10") (pin "46") (pinfunction "VSSQ3_46") (pintype "power_in"))
      (node (ref "U10") (pin "52") (pinfunction "VSSQ4_52") (pintype "power_in"))
      (node (ref "U10") (pin "54") (pinfunction "VSS3_54") (pintype "power_in"))
      (node (ref "U10") (pin "6") (pinfunction "VSSQ1_6") (pintype "power_in"))
      (node (ref "U11") (pin "4") (pinfunction "GND_4") (pintype "passive"))
    )
    (net (code "66") (name "Net-(D11-A)") (class "Default")
      (node (ref "D11") (pin "1") (pinfunction "A_1") (pintype "passive"))
      (node (ref "R43") (pin "2") (pinfunction "2_2") (pintype "passive"))
    )
    (net (code "67") (name "Net-(D12-A)") (class "Default")
      (node (ref "D12") (pin "1") (pinfunction "A_1") (pintype "passive"))
      (node (ref "R44") (pin "2") (pinfunction "2_2") (pintype "passive"))
    )
    (net (code "68") (name "Net-(J6-Pad1)") (class "Default")
      (node (ref "J6") (pin "1") (pinfunction "1_1") (pintype "passive"))
      (node (ref "R32") (pin "2") (pinfunction "2_2") (pintype "passive"))
    )
    (net (code "69") (name "Net-(J7-Pad1)") (class "Default")
      (node (ref "J7") (pin "1") (pinfunction "1_1") (pintype "passive"))
      (node (ref "R33") (pin "2") (pinfunction "2_2") (pintype "passive"))
    )
    (net (code "70") (name "Net-(J8-Pad1)") (class "Default")
      (node (ref "J8") (pin "1") (pinfunction "1_1") (pintype "passive"))
      (node (ref "R35") (pin "2") (pinfunction "2_2") (pintype "passive"))
    )
    (net (code "71") (name "Net-(J9-Pad1)") (class "Default")
      (node (ref "J9") (pin "1") (pinfunction "1_1") (pintype "passive"))
      (node (ref "R40") (pin "2") (pinfunction "2_2") (pintype "passive"))
    )
    (net (code "72") (name "Net-(K6-Pad2)") (class "Default")
      (node (ref "K6") (pin "2") (pinfunction "2_2") (pintype "passive"))
      (node (ref "R52") (pin "1") (pinfunction "1_1") (pintype "passive"))
      (node (ref "R56") (pin "2") (pinfunction "2_2") (pintype "passive"))
    )
    (net (code "73") (name "Net-(T1-B)") (class "Default")
      (node (ref "R52") (pin "2") (pinfunction "2_2") (pintype "passive"))
      (node (ref "T1") (pin "1") (pinfunction "B_1") (pintype "passive"))
    )
    (net (code "74") (name "SDRAM_3V3") (class "Default")
      (node (ref "C70") (pin "1") (pinfunction "1_1") (pintype "passive"))
      (node (ref "C71") (pin "1") (pinfunction "1_1") (pintype "passive"))
      (node (ref "C72") (pin "1") (pinfunction "1_1") (pintype "passive"))
      (node (ref "C73") (pin "1") (pinfunction "1_1") (pintype "passive"))
      (node (ref "C74") (pin "1") (pinfunction "1_1") (pintype "passive"))
      (node (ref "C75") (pin "1") (pinfunction "1_1") (pintype "passive"))
      (node (ref "C76") (pin "1") (pinfunction "1_1") (pintype "passive"))
      (node (ref "C77") (pin "1") (pinfunction "1_1") (pintype "passive"))
      (node (ref "C78") (pin "1") (pinfunction "1_1") (pintype "passive"))
      (node (ref "K6") (pin "1") (pinfunction "1_1") (pintype "passive"))
      (node (ref "R41") (pin "2") (pinfunction "2_2") (pintype "passive"))
      (node (ref "R49") (pin "1") (pinfunction "1_1") (pintype "passive"))
      (node (ref "U10") (pin "1") (pinfunction "VDD1_1") (pintype "power_in"))
      (node (ref "U10") (pin "14") (pinfunction "VDD2_14") (pintype "power_in"))
      (node (ref "U10") (pin "27") (pinfunction "VDD3_27") (pintype "power_in"))
      (node (ref "U10") (pin "3") (pinfunction "VDDQ1_3") (pintype "power_in"))
      (node (ref "U10") (pin "43") (pinfunction "VDDQ3_43") (pintype "power_in"))
      (node (ref "U10") (pin "49") (pinfunction "VDDQ4_49") (pintype "power_in"))
      (node (ref "U10") (pin "9") (pinfunction "VDDQ2_9") (pintype "power_in"))
    )
    (net (code "75") (name "unconnected-(J5-NC-Pad1)") (class "Default")
      (node (ref "J5") (pin "1") (pinfunction "NC_1") (pintype "passive+no_connect"))
    )
    (net (code "76") (name "unconnected-(J5-Z-Pad6)") (class "Default")
      (node (ref "J5") (pin "6") (pinfunction "Z_6") (pintype "passive+no_connect"))
    )
    (net (code "77") (name "unconnected-(U10-NC_E2-Pad40)") (class "Default")
      (node (ref "U10") (pin "40") (pinfunction "NC_E2_40") (pintype "passive+no_connect"))
    )
  )
)
